# zOUT_v_1_0.net
KiCad netlist of a schematic drawn in EAGLE
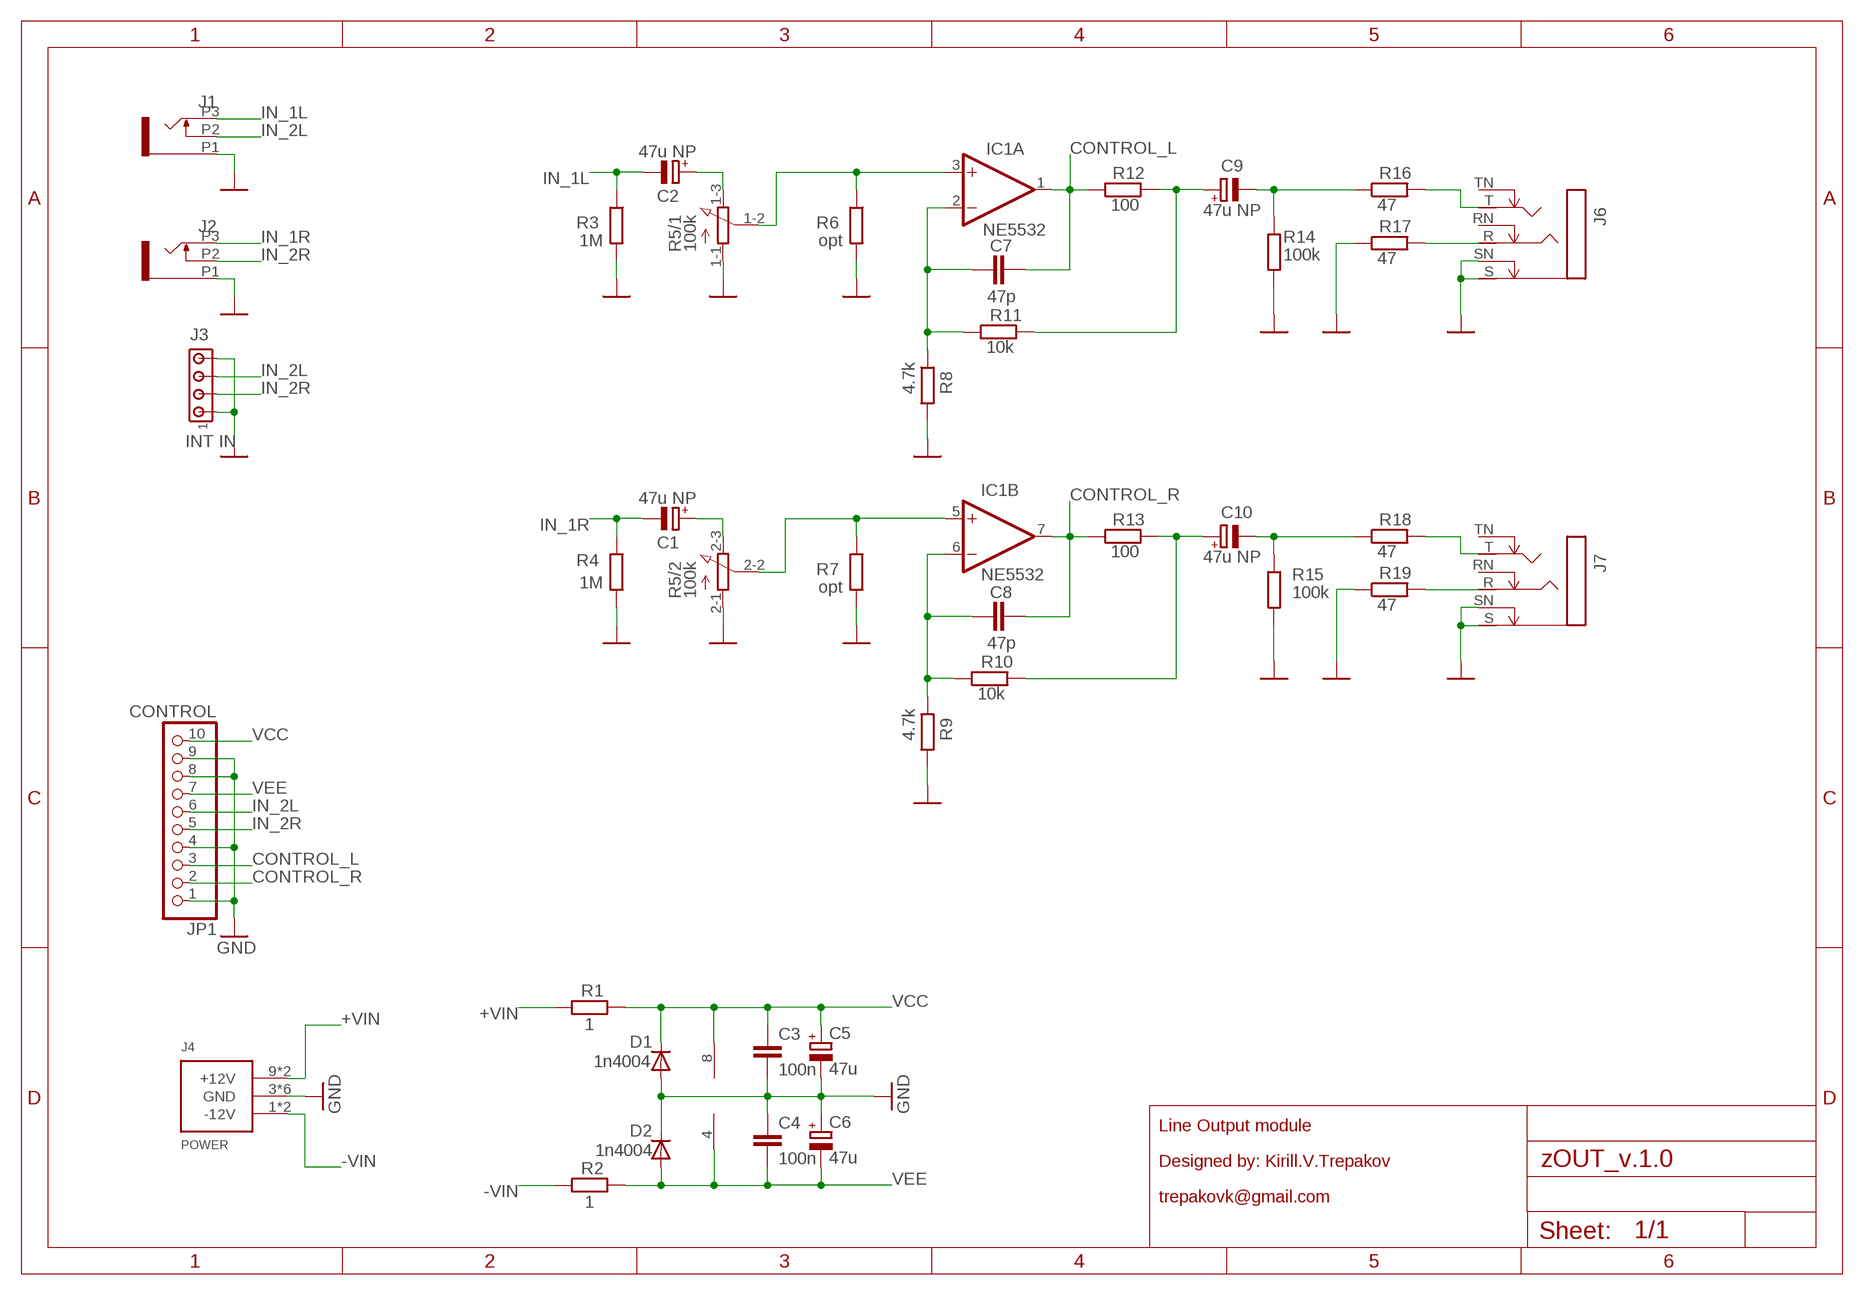
[diagram p0: schematic, sheet 1]

(export (version "E")
  (design (tool "Eeschema 10.0.6"))
  (components
    (comp (ref "C1")
      (value "47u NP")
      (footprint "eagle-import:E2,5-6")
      (libsource (lib "eagle-import") (part "CPOL-EUE2.5-6"))
    )
    (comp (ref "C2")
      (value "47u NP")
      (footprint "eagle-import:E2,5-6")
      (libsource (lib "eagle-import") (part "CPOL-EUE2.5-6"))
    )
    (comp (ref "C3")
      (value "100n")
      (footprint "eagle-import:C050-024X044")
      (libsource (lib "eagle-import") (part "C-EU050-024X044"))
    )
    (comp (ref "C4")
      (value "100n")
      (footprint "eagle-import:C050-024X044")
      (libsource (lib "eagle-import") (part "C-EU050-024X044"))
    )
    (comp (ref "C5")
      (value "47u")
      (footprint "eagle-import:E2,5-5")
      (libsource (lib "eagle-import") (part "CPOL-EUE2.5-5"))
    )
    (comp (ref "C6")
      (value "47u")
      (footprint "eagle-import:E2,5-5")
      (libsource (lib "eagle-import") (part "CPOL-EUE2.5-5"))
    )
    (comp (ref "C7")
      (value "47p")
      (footprint "eagle-import:C050-024X044")
      (libsource (lib "eagle-import") (part "C-EU050-024X044"))
    )
    (comp (ref "C8")
      (value "47p")
      (footprint "eagle-import:C050-024X044")
      (libsource (lib "eagle-import") (part "C-EU050-024X044"))
    )
    (comp (ref "C9")
      (value "47u NP")
      (footprint "eagle-import:E2,5-6")
      (libsource (lib "eagle-import") (part "CPOL-EUE2.5-6"))
    )
    (comp (ref "C10")
      (value "47u NP")
      (footprint "eagle-import:E2,5-6")
      (libsource (lib "eagle-import") (part "CPOL-EUE2.5-6"))
    )
    (comp (ref "D1")
      (value "1n4004")
      (footprint "eagle-import:DO41-7.6")
      (libsource (lib "eagle-import") (part "1N4004{dblquote}"))
    )
    (comp (ref "D2")
      (value "1n4004")
      (footprint "eagle-import:DO41-7.6")
      (libsource (lib "eagle-import") (part "1N4004{dblquote}"))
    )
    (comp (ref "IC1")
      (value "NE5532")
      (footprint "eagle-import:DIL08")
      (libsource (lib "eagle-import") (part "TL072P"))
    )
    (comp (ref "J1")
      (value "IN L")
      (footprint "eagle-import:WQP-PJ302M_JACK")
      (libsource (lib "eagle-import") (part "WQP-PJ302M_JACK"))
    )
    (comp (ref "J2")
      (value "IN R")
      (footprint "eagle-import:WQP-PJ302M_JACK")
      (libsource (lib "eagle-import") (part "WQP-PJ302M_JACK"))
    )
    (comp (ref "J3")
      (value "INT IN")
      (footprint "eagle-import:10X04MTA")
      (libsource (lib "eagle-import") (part "MTA04-100"))
    )
    (comp (ref "J4")
      (value "POWER")
      (footprint "eagle-import:POWER_10")
      (libsource (lib "eagle-import") (part "POWER_SIMPLE10"))
    )
    (comp (ref "J6")
      (value "OUT L")
      (footprint "eagle-import:NMJ6HC-S")
      (libsource (lib "eagle-import") (part "STEREOSW1"))
    )
    (comp (ref "J7")
      (value "OUT R")
      (footprint "eagle-import:NMJ6HC-S")
      (libsource (lib "eagle-import") (part "STEREOSW1"))
    )
    (comp (ref "JP1")
      (value "CONTROL")
      (footprint "eagle-import:1X10")
      (libsource (lib "eagle-import") (part "PINHD-1X10"))
    )
    (comp (ref "R1")
      (value "1")
      (footprint "eagle-import:0204_7")
      (libsource (lib "eagle-import") (part "R-EU_0204/7"))
    )
    (comp (ref "R2")
      (value "1")
      (footprint "eagle-import:0204_7")
      (libsource (lib "eagle-import") (part "R-EU_0204/7"))
    )
    (comp (ref "R3")
      (value "1M")
      (footprint "eagle-import:0204_7")
      (libsource (lib "eagle-import") (part "R-EU_0204/7"))
    )
    (comp (ref "R4")
      (value "1M")
      (footprint "eagle-import:0204_7")
      (libsource (lib "eagle-import") (part "R-EU_0204/7"))
    )
    (comp (ref "R5")
      (value "100k")
      (footprint "eagle-import:3RP_1610G")
      (libsource (lib "eagle-import") (part "3RP/1610G"))
    )
    (comp (ref "R6")
      (value "opt")
      (footprint "eagle-import:0204_7")
      (libsource (lib "eagle-import") (part "R-EU_0204/7"))
    )
    (comp (ref "R7")
      (value "opt")
      (footprint "eagle-import:0204_7")
      (libsource (lib "eagle-import") (part "R-EU_0204/7"))
    )
    (comp (ref "R8")
      (value "4.7k")
      (footprint "eagle-import:0204_7")
      (libsource (lib "eagle-import") (part "R-EU_0204/7"))
    )
    (comp (ref "R9")
      (value "4.7k")
      (footprint "eagle-import:0204_7")
      (libsource (lib "eagle-import") (part "R-EU_0204/7"))
    )
    (comp (ref "R10")
      (value "10k")
      (footprint "eagle-import:0204_7")
      (libsource (lib "eagle-import") (part "R-EU_0204/7"))
    )
    (comp (ref "R11")
      (value "10k")
      (footprint "eagle-import:0204_7")
      (libsource (lib "eagle-import") (part "R-EU_0204/7"))
    )
    (comp (ref "R12")
      (value "100")
      (footprint "eagle-import:0204_7")
      (libsource (lib "eagle-import") (part "R-EU_0204/7"))
    )
    (comp (ref "R13")
      (value "100")
      (footprint "eagle-import:0204_7")
      (libsource (lib "eagle-import") (part "R-EU_0204/7"))
    )
    (comp (ref "R14")
      (value "100k")
      (footprint "eagle-import:0204_7")
      (libsource (lib "eagle-import") (part "R-EU_0204/7"))
    )
    (comp (ref "R15")
      (value "100k")
      (footprint "eagle-import:0204_7")
      (libsource (lib "eagle-import") (part "R-EU_0204/7"))
    )
    (comp (ref "R16")
      (value "47")
      (footprint "eagle-import:0204_7")
      (libsource (lib "eagle-import") (part "R-EU_0204/7"))
    )
    (comp (ref "R17")
      (value "47")
      (footprint "eagle-import:0204_7")
      (libsource (lib "eagle-import") (part "R-EU_0204/7"))
    )
    (comp (ref "R18")
      (value "47")
      (footprint "eagle-import:0204_7")
      (libsource (lib "eagle-import") (part "R-EU_0204/7"))
    )
    (comp (ref "R19")
      (value "47")
      (footprint "eagle-import:0204_7")
      (libsource (lib "eagle-import") (part "R-EU_0204/7"))
    )
  )
  (nets
    (net (code "1") (name "/+VIN") (class "Default")
      (node (ref "J4") (pin "10") (pinfunction "+12V_10") (pintype "bidirectional"))
      (node (ref "J4") (pin "9") (pinfunction "+12V_9") (pintype "bidirectional"))
      (node (ref "R1") (pin "1") (pinfunction "1_1") (pintype "passive"))
    )
    (net (code "2") (name "/-VIN") (class "Default")
      (node (ref "J4") (pin "1") (pinfunction "-12V_1") (pintype "bidirectional"))
      (node (ref "J4") (pin "2") (pinfunction "-12V_2") (pintype "bidirectional"))
      (node (ref "R2") (pin "1") (pinfunction "1_1") (pintype "passive"))
    )
    (net (code "3") (name "/CONTROL_L") (class "Default")
      (node (ref "C7") (pin "2") (pinfunction "2_2") (pintype "passive"))
      (node (ref "IC1") (pin "1") (pinfunction "OUT_1") (pintype "output"))
      (node (ref "JP1") (pin "3") (pinfunction "3_3") (pintype "passive"))
      (node (ref "R12") (pin "1") (pinfunction "1_1") (pintype "passive"))
    )
    (net (code "4") (name "/CONTROL_R") (class "Default")
      (node (ref "C8") (pin "2") (pinfunction "2_2") (pintype "passive"))
      (node (ref "IC1") (pin "7") (pinfunction "OUT_7") (pintype "output"))
      (node (ref "JP1") (pin "2") (pinfunction "2_2") (pintype "passive"))
      (node (ref "R13") (pin "1") (pinfunction "1_1") (pintype "passive"))
    )
    (net (code "5") (name "/IN_1L") (class "Default")
      (node (ref "C2") (pin "-") (pinfunction "-_-") (pintype "passive"))
      (node (ref "J1") (pin "P3") (pinfunction "3_P3") (pintype "passive"))
      (node (ref "R3") (pin "1") (pinfunction "1_1") (pintype "passive"))
    )
    (net (code "6") (name "/IN_1R") (class "Default")
      (node (ref "C1") (pin "-") (pinfunction "-_-") (pintype "passive"))
      (node (ref "J2") (pin "P3") (pinfunction "3_P3") (pintype "passive"))
      (node (ref "R4") (pin "1") (pinfunction "1_1") (pintype "passive"))
    )
    (net (code "7") (name "/IN_2L") (class "Default")
      (node (ref "J1") (pin "P2") (pinfunction "2_P2") (pintype "passive"))
      (node (ref "J3") (pin "3") (pinfunction "3_3") (pintype "passive"))
      (node (ref "JP1") (pin "6") (pinfunction "6_6") (pintype "passive"))
    )
    (net (code "8") (name "/IN_2R") (class "Default")
      (node (ref "J2") (pin "P2") (pinfunction "2_P2") (pintype "passive"))
      (node (ref "J3") (pin "2") (pinfunction "2_2") (pintype "passive"))
      (node (ref "JP1") (pin "5") (pinfunction "5_5") (pintype "passive"))
    )
    (net (code "9") (name "/VCC") (class "Default")
      (node (ref "C3") (pin "1") (pinfunction "1_1") (pintype "passive"))
      (node (ref "C5") (pin "+") (pinfunction "+_+") (pintype "passive"))
      (node (ref "D1") (pin "C") (pinfunction "C_C") (pintype "passive"))
      (node (ref "IC1") (pin "8") (pinfunction "V+_8") (pintype "power_in"))
      (node (ref "JP1") (pin "10") (pinfunction "10_10") (pintype "passive"))
      (node (ref "R1") (pin "2") (pinfunction "2_2") (pintype "passive"))
    )
    (net (code "10") (name "/VEE") (class "Default")
      (node (ref "C4") (pin "2") (pinfunction "2_2") (pintype "passive"))
      (node (ref "C6") (pin "-") (pinfunction "-_-") (pintype "passive"))
      (node (ref "D2") (pin "A") (pinfunction "A_A") (pintype "passive"))
      (node (ref "IC1") (pin "4") (pinfunction "V-_4") (pintype "power_in"))
      (node (ref "JP1") (pin "7") (pinfunction "7_7") (pintype "passive"))
      (node (ref "R2") (pin "2") (pinfunction "2_2") (pintype "passive"))
    )
    (net (code "11") (name "GND") (class "Default")
      (node (ref "C3") (pin "2") (pinfunction "2_2") (pintype "passive"))
      (node (ref "C4") (pin "1") (pinfunction "1_1") (pintype "passive"))
      (node (ref "C5") (pin "-") (pinfunction "-_-") (pintype "passive"))
      (node (ref "C6") (pin "+") (pinfunction "+_+") (pintype "passive"))
      (node (ref "D1") (pin "A") (pinfunction "A_A") (pintype "passive"))
      (node (ref "D2") (pin "C") (pinfunction "C_C") (pintype "passive"))
      (node (ref "J1") (pin "P1") (pinfunction "1_P1") (pintype "passive"))
      (node (ref "J2") (pin "P1") (pinfunction "1_P1") (pintype "passive"))
      (node (ref "J3") (pin "1") (pinfunction "1_1") (pintype "passive"))
      (node (ref "J3") (pin "4") (pinfunction "4_4") (pintype "passive"))
      (node (ref "J4") (pin "3") (pinfunction "GND_3") (pintype "bidirectional"))
      (node (ref "J4") (pin "4") (pinfunction "GND_4") (pintype "bidirectional"))
      (node (ref "J4") (pin "5") (pinfunction "GND_5") (pintype "bidirectional"))
      (node (ref "J4") (pin "6") (pinfunction "GND_6") (pintype "bidirectional"))
      (node (ref "J4") (pin "7") (pinfunction "GND_7") (pintype "bidirectional"))
      (node (ref "J4") (pin "8") (pinfunction "GND_8") (pintype "bidirectional"))
      (node (ref "J6") (pin "S") (pinfunction "S_S") (pintype "passive"))
      (node (ref "J6") (pin "SN") (pinfunction "SN_SN") (pintype "passive"))
      (node (ref "J7") (pin "S") (pinfunction "S_S") (pintype "passive"))
      (node (ref "J7") (pin "SN") (pinfunction "SN_SN") (pintype "passive"))
      (node (ref "JP1") (pin "1") (pinfunction "1_1") (pintype "passive"))
      (node (ref "JP1") (pin "4") (pinfunction "4_4") (pintype "passive"))
      (node (ref "JP1") (pin "8") (pinfunction "8_8") (pintype "passive"))
      (node (ref "JP1") (pin "9") (pinfunction "9_9") (pintype "passive"))
      (node (ref "R14") (pin "2") (pinfunction "2_2") (pintype "passive"))
      (node (ref "R15") (pin "2") (pinfunction "2_2") (pintype "passive"))
      (node (ref "R17") (pin "1") (pinfunction "1_1") (pintype "passive"))
      (node (ref "R19") (pin "1") (pinfunction "1_1") (pintype "passive"))
      (node (ref "R3") (pin "2") (pinfunction "2_2") (pintype "passive"))
      (node (ref "R4") (pin "2") (pinfunction "2_2") (pintype "passive"))
      (node (ref "R5") (pin "1-1") (pinfunction "A_1-1") (pintype "passive"))
      (node (ref "R5") (pin "2-1") (pinfunction "A_2-1") (pintype "passive"))
      (node (ref "R6") (pin "2") (pinfunction "2_2") (pintype "passive"))
      (node (ref "R7") (pin "2") (pinfunction "2_2") (pintype "passive"))
      (node (ref "R8") (pin "2") (pinfunction "2_2") (pintype "passive"))
      (node (ref "R9") (pin "2") (pinfunction "2_2") (pintype "passive"))
    )
    (net (code "12") (name "Net-(C9-Pad+)") (class "Default")
      (node (ref "C9") (pin "+") (pinfunction "+_+") (pintype "passive"))
      (node (ref "R11") (pin "2") (pinfunction "2_2") (pintype "passive"))
      (node (ref "R12") (pin "2") (pinfunction "2_2") (pintype "passive"))
    )
    (net (code "13") (name "Net-(C9-Pad-)") (class "Default")
      (node (ref "C9") (pin "-") (pinfunction "-_-") (pintype "passive"))
      (node (ref "R14") (pin "1") (pinfunction "1_1") (pintype "passive"))
      (node (ref "R16") (pin "1") (pinfunction "1_1") (pintype "passive"))
    )
    (net (code "14") (name "Net-(C10-Pad+)") (class "Default")
      (node (ref "C10") (pin "+") (pinfunction "+_+") (pintype "passive"))
      (node (ref "R10") (pin "2") (pinfunction "2_2") (pintype "passive"))
      (node (ref "R13") (pin "2") (pinfunction "2_2") (pintype "passive"))
    )
    (net (code "15") (name "Net-(C10-Pad-)") (class "Default")
      (node (ref "C10") (pin "-") (pinfunction "-_-") (pintype "passive"))
      (node (ref "R15") (pin "1") (pinfunction "1_1") (pintype "passive"))
      (node (ref "R18") (pin "1") (pinfunction "1_1") (pintype "passive"))
    )
    (net (code "16") (name "Net-(IC1A-+IN)") (class "Default")
      (node (ref "IC1") (pin "3") (pinfunction "+IN_3") (pintype "input"))
      (node (ref "R5") (pin "1-2") (pinfunction "S_1-2") (pintype "passive"))
      (node (ref "R6") (pin "1") (pinfunction "1_1") (pintype "passive"))
    )
    (net (code "17") (name "Net-(IC1A--IN)") (class "Default")
      (node (ref "C7") (pin "1") (pinfunction "1_1") (pintype "passive"))
      (node (ref "IC1") (pin "2") (pinfunction "-IN_2") (pintype "input"))
      (node (ref "R11") (pin "1") (pinfunction "1_1") (pintype "passive"))
      (node (ref "R8") (pin "1") (pinfunction "1_1") (pintype "passive"))
    )
    (net (code "18") (name "Net-(IC1B-+IN)") (class "Default")
      (node (ref "IC1") (pin "5") (pinfunction "+IN_5") (pintype "input"))
      (node (ref "R5") (pin "2-2") (pinfunction "S_2-2") (pintype "passive"))
      (node (ref "R7") (pin "1") (pinfunction "1_1") (pintype "passive"))
    )
    (net (code "19") (name "Net-(IC1B--IN)") (class "Default")
      (node (ref "C8") (pin "1") (pinfunction "1_1") (pintype "passive"))
      (node (ref "IC1") (pin "6") (pinfunction "-IN_6") (pintype "input"))
      (node (ref "R10") (pin "1") (pinfunction "1_1") (pintype "passive"))
      (node (ref "R9") (pin "1") (pinfunction "1_1") (pintype "passive"))
    )
    (net (code "20") (name "Net-(J6-PadR)") (class "Default")
      (node (ref "J6") (pin "R") (pinfunction "R_R") (pintype "passive"))
      (node (ref "R17") (pin "2") (pinfunction "2_2") (pintype "passive"))
    )
    (net (code "21") (name "Net-(J6-PadT)") (class "Default")
      (node (ref "J6") (pin "T") (pinfunction "T_T") (pintype "passive"))
      (node (ref "R16") (pin "2") (pinfunction "2_2") (pintype "passive"))
    )
    (net (code "22") (name "Net-(J7-PadR)") (class "Default")
      (node (ref "J7") (pin "R") (pinfunction "R_R") (pintype "passive"))
      (node (ref "R19") (pin "2") (pinfunction "2_2") (pintype "passive"))
    )
    (net (code "23") (name "Net-(J7-PadT)") (class "Default")
      (node (ref "J7") (pin "T") (pinfunction "T_T") (pintype "passive"))
      (node (ref "R18") (pin "2") (pinfunction "2_2") (pintype "passive"))
    )
    (net (code "24") (name "Net-(R5A-E)") (class "Default")
      (node (ref "C2") (pin "+") (pinfunction "+_+") (pintype "passive"))
      (node (ref "R5") (pin "1-3") (pinfunction "E_1-3") (pintype "passive"))
    )
    (net (code "25") (name "Net-(R5B-E)") (class "Default")
      (node (ref "C1") (pin "+") (pinfunction "+_+") (pintype "passive"))
      (node (ref "R5") (pin "2-3") (pinfunction "E_2-3") (pintype "passive"))
    )
    (net (code "26") (name "unconnected-(J6-PadRN)") (class "Default")
      (node (ref "J6") (pin "RN") (pinfunction "RN_RN") (pintype "passive"))
    )
    (net (code "27") (name "unconnected-(J6-PadTN)") (class "Default")
      (node (ref "J6") (pin "TN") (pinfunction "TN_TN") (pintype "passive"))
    )
    (net (code "28") (name "unconnected-(J7-PadRN)") (class "Default")
      (node (ref "J7") (pin "RN") (pinfunction "RN_RN") (pintype "passive"))
    )
    (net (code "29") (name "unconnected-(J7-PadTN)") (class "Default")
      (node (ref "J7") (pin "TN") (pinfunction "TN_TN") (pintype "passive"))
    )
  )
)
